# ProPrj_New_Project_2026-05-24_21-45-30_2.net
KiCad netlist of a schematic drawn in EasyEDA Pro
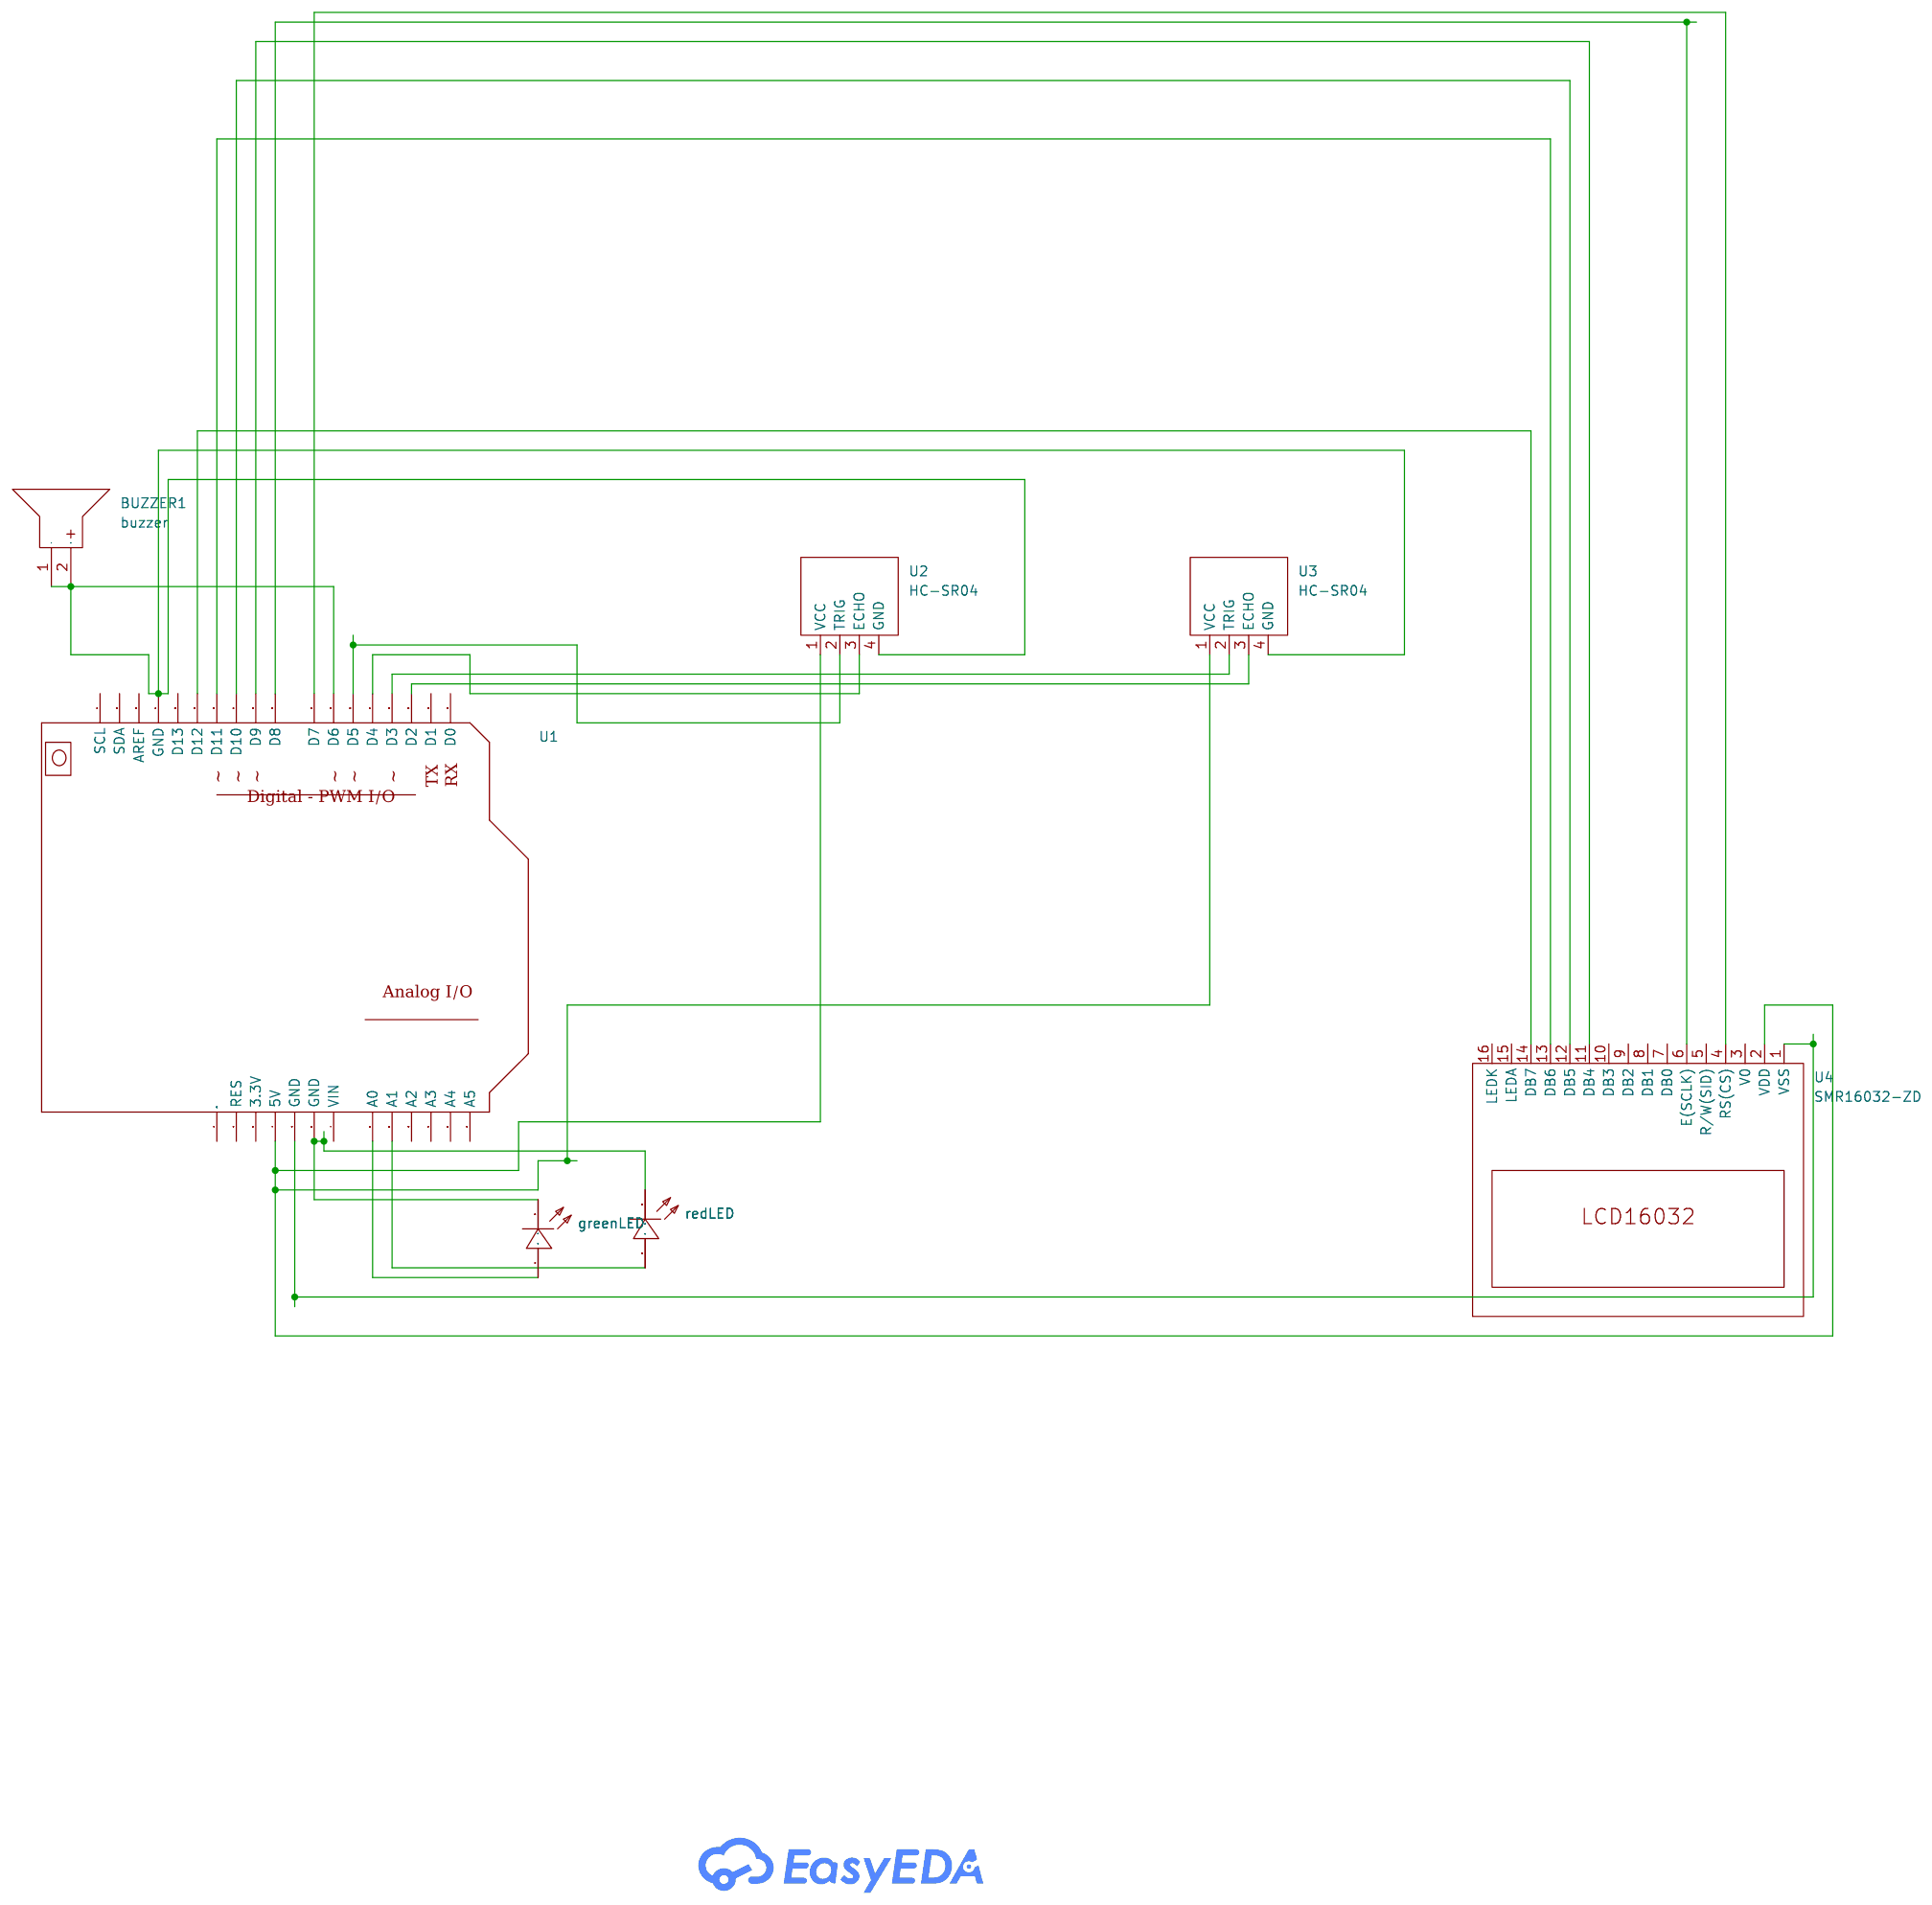
[diagram p0: schematic sheet]

(export (version "E")
  (design (tool "Eeschema 10.0.6"))
  (components
    (comp (ref "BUZZER1")
      (value "buzzer")
      (footprint "easyedapro:BUZ-TH_BD12.0-P6.00-D0.9-RD")
      (libsource (lib "easyedapro") (part "BUZZER"))
    )
    (comp (ref "greenLED")
      (value "KT-0805G")
      (footprint "easyedapro:LED0805-R-RD")
      (fields (field (name "Manufacturer") "KENTO"))
      (libsource (lib "easyedapro") (part "0805G (Green)"))
    )
    (comp (ref "redLED")
      (value "KT-0805G")
      (footprint "easyedapro:LED0805-R-RD")
      (fields (field (name "Manufacturer") "KENTO"))
      (libsource (lib "easyedapro") (part "0805G (Green)"))
    )
    (comp (ref "U1")
      (value "~")
      (footprint "easyedapro:ARDUINO UNO R3 FOOTPRINT")
      (libsource (lib "easyedapro") (part "Arduino UNO R3 Footprint"))
    )
    (comp (ref "U2")
      (value "HC-SR04")
      (footprint "easyedapro:TH_HC-SR04V")
      (fields (field (name "Manufacturer") "Universal Microelectronics"))
      (libsource (lib "easyedapro") (part "HC-SR04"))
    )
    (comp (ref "U3")
      (value "HC-SR04")
      (footprint "easyedapro:TH_HC-SR04V")
      (fields (field (name "Manufacturer") "Universal Microelectronics"))
      (libsource (lib "easyedapro") (part "HC-SR04"))
    )
    (comp (ref "U4")
      (value "SMR16032-ZD")
      (footprint "easyedapro:LCD-TH_SMR16032-ZD")
      (libsource (lib "easyedapro") (part "SMR16032-ZD"))
    )
  )
  (nets
    (net (code "1") (name "Net-(BUZZER1-+)") (class "Default")
      (node (ref "BUZZER1") (pin "1") (pinfunction "-_1") (pintype "unspecified"))
      (node (ref "BUZZER1") (pin "2") (pinfunction "+_2") (pintype "unspecified"))
      (node (ref "U1") (pin "17") (pinfunction "GND_17") (pintype "input"))
      (node (ref "U1") (pin "25") (pinfunction "D6_25") (pintype "input"))
      (node (ref "U2") (pin "4") (pinfunction "GND_4") (pintype "unspecified"))
      (node (ref "U3") (pin "4") (pinfunction "GND_4") (pintype "unspecified"))
    )
    (net (code "2") (name "Net-(U1-5V)") (class "Default")
      (node (ref "U1") (pin "4") (pinfunction "5V_4") (pintype "input"))
      (node (ref "U2") (pin "1") (pinfunction "VCC_1") (pintype "unspecified"))
      (node (ref "U3") (pin "1") (pinfunction "VCC_1") (pintype "unspecified"))
      (node (ref "U4") (pin "2") (pinfunction "VDD_2") (pintype "unspecified"))
    )
    (net (code "3") (name "Net-(U1-A0)") (class "Default")
      (node (ref "U1") (pin "8") (pinfunction "A0_8") (pintype "input"))
      (node (ref "greenLED") (pin "1") (pinfunction "A_1") (pintype "unspecified"))
    )
    (net (code "4") (name "Net-(U1-A1)") (class "Default")
      (node (ref "U1") (pin "9") (pinfunction "A1_9") (pintype "input"))
      (node (ref "redLED") (pin "1") (pinfunction "A_1") (pintype "unspecified"))
    )
    (net (code "5") (name "Net-(U1-D2)") (class "Default")
      (node (ref "U1") (pin "29") (pinfunction "D2_29") (pintype "input"))
      (node (ref "U3") (pin "3") (pinfunction "ECHO_3") (pintype "unspecified"))
    )
    (net (code "6") (name "Net-(U1-D3)") (class "Default")
      (node (ref "U1") (pin "28") (pinfunction "D3_28") (pintype "input"))
      (node (ref "U3") (pin "2") (pinfunction "TRIG_2") (pintype "unspecified"))
    )
    (net (code "7") (name "Net-(U1-D4)") (class "Default")
      (node (ref "U1") (pin "27") (pinfunction "D4_27") (pintype "input"))
      (node (ref "U2") (pin "3") (pinfunction "ECHO_3") (pintype "unspecified"))
    )
    (net (code "8") (name "Net-(U1-D5)") (class "Default")
      (node (ref "U1") (pin "26") (pinfunction "D5_26") (pintype "input"))
      (node (ref "U2") (pin "2") (pinfunction "TRIG_2") (pintype "unspecified"))
    )
    (net (code "9") (name "Net-(U1-D7)") (class "Default")
      (node (ref "U1") (pin "24") (pinfunction "D7_24") (pintype "input"))
      (node (ref "U4") (pin "4") (pinfunction "RS(CS)_4") (pintype "unspecified"))
    )
    (net (code "10") (name "Net-(U1-D8)") (class "Default")
      (node (ref "U1") (pin "23") (pinfunction "D8_23") (pintype "input"))
      (node (ref "U4") (pin "6") (pinfunction "E(SCLK)_6") (pintype "unspecified"))
    )
    (net (code "11") (name "Net-(U1-D9)") (class "Default")
      (node (ref "U1") (pin "22") (pinfunction "D9_22") (pintype "input"))
      (node (ref "U4") (pin "11") (pinfunction "DB4_11") (pintype "unspecified"))
    )
    (net (code "12") (name "Net-(U1-D10)") (class "Default")
      (node (ref "U1") (pin "21") (pinfunction "D10_21") (pintype "input"))
      (node (ref "U4") (pin "12") (pinfunction "DB5_12") (pintype "unspecified"))
    )
    (net (code "13") (name "Net-(U1-D11)") (class "Default")
      (node (ref "U1") (pin "20") (pinfunction "D11_20") (pintype "input"))
      (node (ref "U4") (pin "13") (pinfunction "DB6_13") (pintype "unspecified"))
    )
    (net (code "14") (name "Net-(U1-D12)") (class "Default")
      (node (ref "U1") (pin "19") (pinfunction "D12_19") (pintype "input"))
      (node (ref "U4") (pin "14") (pinfunction "DB7_14") (pintype "unspecified"))
    )
    (net (code "15") (name "Net-(U4-VSS)") (class "Default")
      (node (ref "U1") (pin "5") (pinfunction "GND_5") (pintype "input"))
      (node (ref "U4") (pin "1") (pinfunction "VSS_1") (pintype "unspecified"))
    )
    (net (code "16") (name "Net-(greenLED-K)") (class "Default")
      (node (ref "U1") (pin "6") (pinfunction "GND_6") (pintype "input"))
      (node (ref "greenLED") (pin "2") (pinfunction "K_2") (pintype "unspecified"))
      (node (ref "redLED") (pin "2") (pinfunction "K_2") (pintype "unspecified"))
    )
    (net (code "17") (name "unconnected-(U1-3.3V-Pad3)") (class "Default")
      (node (ref "U1") (pin "3") (pinfunction "3.3V_3") (pintype "input"))
    )
    (net (code "18") (name "unconnected-(U1-A2-Pad10)") (class "Default")
      (node (ref "U1") (pin "10") (pinfunction "A2_10") (pintype "input"))
    )
    (net (code "19") (name "unconnected-(U1-A3-Pad11)") (class "Default")
      (node (ref "U1") (pin "11") (pinfunction "A3_11") (pintype "input"))
    )
    (net (code "20") (name "unconnected-(U1-A4-Pad12)") (class "Default")
      (node (ref "U1") (pin "12") (pinfunction "A4_12") (pintype "input"))
    )
    (net (code "21") (name "unconnected-(U1-A5-Pad13)") (class "Default")
      (node (ref "U1") (pin "13") (pinfunction "A5_13") (pintype "input"))
    )
    (net (code "22") (name "unconnected-(U1-AREF-Pad16)") (class "Default")
      (node (ref "U1") (pin "16") (pinfunction "AREF_16") (pintype "input"))
    )
    (net (code "23") (name "unconnected-(U1-D0-Pad31)") (class "Default")
      (node (ref "U1") (pin "31") (pinfunction "D0_31") (pintype "input"))
    )
    (net (code "24") (name "unconnected-(U1-D1-Pad30)") (class "Default")
      (node (ref "U1") (pin "30") (pinfunction "D1_30") (pintype "input"))
    )
    (net (code "25") (name "unconnected-(U1-D13-Pad18)") (class "Default")
      (node (ref "U1") (pin "18") (pinfunction "D13_18") (pintype "input"))
    )
    (net (code "26") (name "unconnected-(U1-RES-Pad2)") (class "Default")
      (node (ref "U1") (pin "2") (pinfunction "RES_2") (pintype "input"))
    )
    (net (code "27") (name "unconnected-(U1-SCL-Pad14)") (class "Default")
      (node (ref "U1") (pin "14") (pinfunction "SCL_14") (pintype "input"))
    )
    (net (code "28") (name "unconnected-(U1-SDA-Pad15)") (class "Default")
      (node (ref "U1") (pin "15") (pinfunction "SDA_15") (pintype "input"))
    )
    (net (code "29") (name "unconnected-(U1-VIN-Pad7)") (class "Default")
      (node (ref "U1") (pin "7") (pinfunction "VIN_7") (pintype "input"))
    )
    (net (code "30") (name "unconnected-(U1-blnk-Pad1)") (class "Default")
      (node (ref "U1") (pin "1") (pinfunction "blnk_1") (pintype "input"))
    )
    (net (code "31") (name "unconnected-(U4-DB0-Pad7)") (class "Default")
      (node (ref "U4") (pin "7") (pinfunction "DB0_7") (pintype "unspecified"))
    )
    (net (code "32") (name "unconnected-(U4-DB1-Pad8)") (class "Default")
      (node (ref "U4") (pin "8") (pinfunction "DB1_8") (pintype "unspecified"))
    )
    (net (code "33") (name "unconnected-(U4-DB2-Pad9)") (class "Default")
      (node (ref "U4") (pin "9") (pinfunction "DB2_9") (pintype "unspecified"))
    )
    (net (code "34") (name "unconnected-(U4-DB3-Pad10)") (class "Default")
      (node (ref "U4") (pin "10") (pinfunction "DB3_10") (pintype "unspecified"))
    )
    (net (code "35") (name "unconnected-(U4-LEDA-Pad15)") (class "Default")
      (node (ref "U4") (pin "15") (pinfunction "LEDA_15") (pintype "unspecified"))
    )
    (net (code "36") (name "unconnected-(U4-LEDK-Pad16)") (class "Default")
      (node (ref "U4") (pin "16") (pinfunction "LEDK_16") (pintype "unspecified"))
    )
    (net (code "37") (name "unconnected-(U4-R{slash}W(SID)-Pad5)") (class "Default")
      (node (ref "U4") (pin "5") (pinfunction "R/W(SID)_5") (pintype "unspecified"))
    )
    (net (code "38") (name "unconnected-(U4-V0-Pad3)") (class "Default")
      (node (ref "U4") (pin "3") (pinfunction "V0_3") (pintype "unspecified"))
    )
  )
)
